# 7_Current_Sensing.net
KiCad netlist of a schematic drawn in Altium Designer
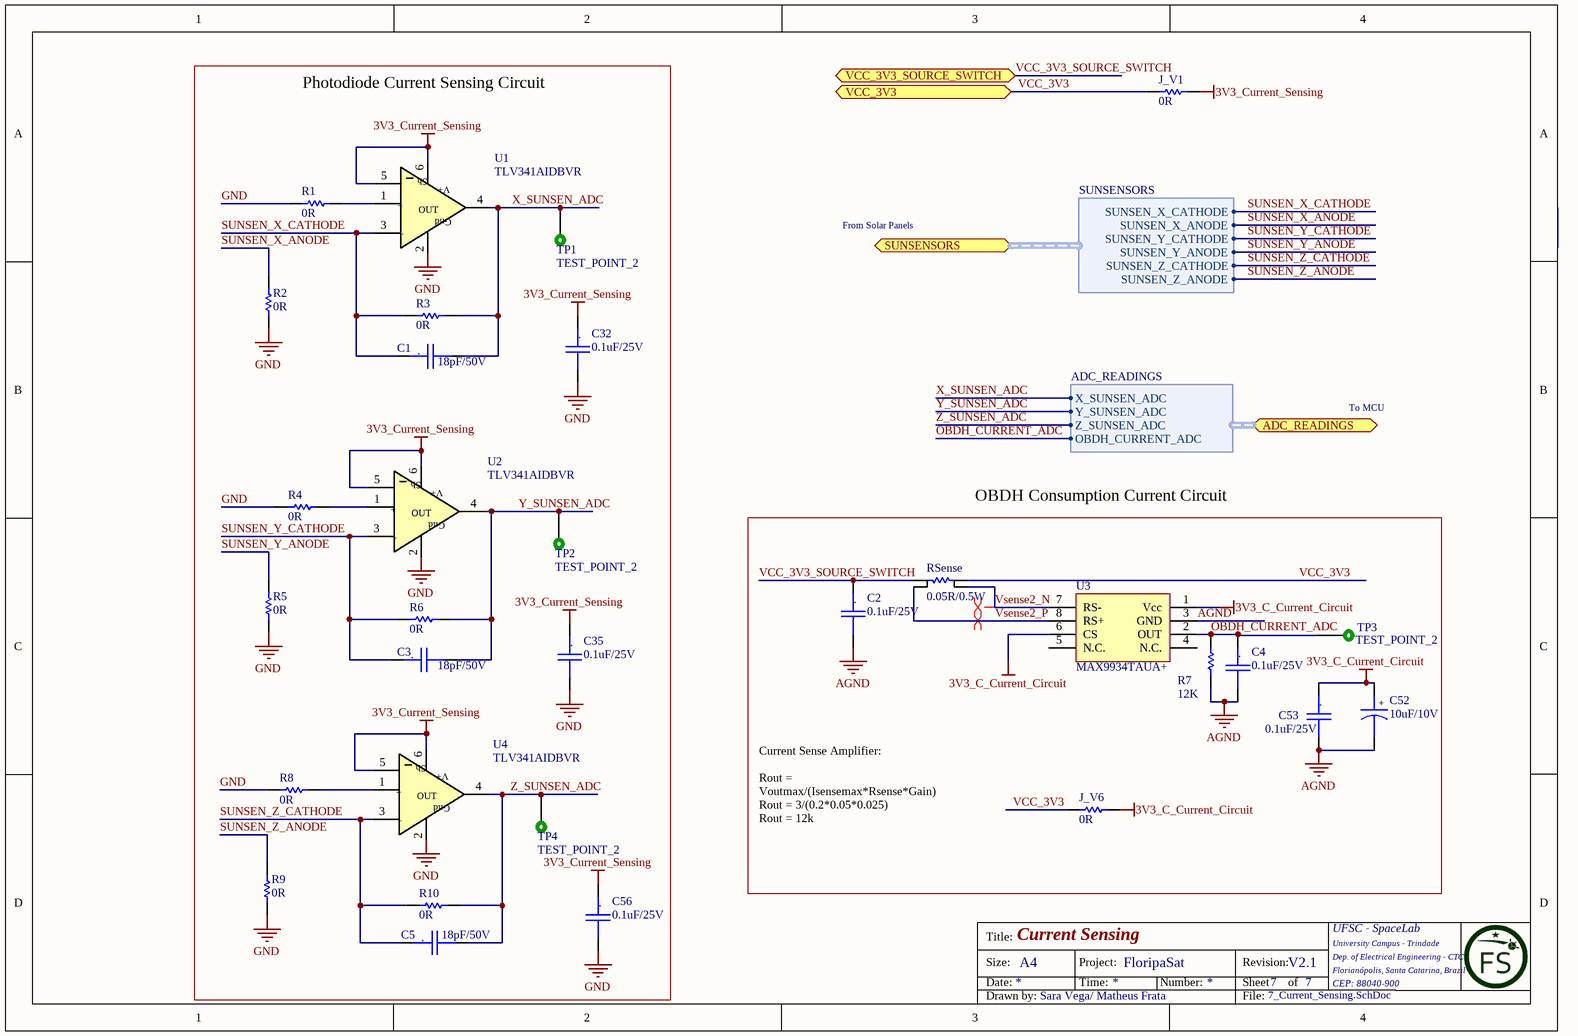
[diagram p0: 7_Current_Sensing.SchDoc]

(export (version "E")
  (design (tool "Eeschema 10.0.6"))
  (components
    (comp (ref "C1")
      (value "18pF/50V")
      (footprint "CC0805")
      (description "CAP CER 18pF 50V 5% X7R 0805")
      (fields (field (name "PARTNUMBER") "CC0805JRNPO9BN180"))
      (libsource (lib "FloripaSatSchlib") (part "Cap_Cer_X7R_18pF_50V_0805"))
    )
    (comp (ref "C2")
      (value "0.1uF/25V")
      (footprint "CC0805")
      (description "CAP CER 0.1UF 25V 10% X7R 0805")
      (fields (field (name "PARTNUMBER") "CC0805KRX7R8BB104"))
      (libsource (lib "FloripaSatSchlib") (part "Cap_Cer_X7R_0.1uF_25V_0805"))
    )
    (comp (ref "C3")
      (value "18pF/50V")
      (footprint "CC0805")
      (description "CAP CER 18pF 50V 5% X7R 0805")
      (fields (field (name "PARTNUMBER") "CC0805JRNPO9BN180"))
      (libsource (lib "FloripaSatSchlib") (part "Cap_Cer_X7R_18pF_50V_0805"))
    )
    (comp (ref "C4")
      (value "0.1uF/25V")
      (footprint "CC0805")
      (description "CAP CER 0.1UF 25V 10% X7R 0805")
      (fields (field (name "PARTNUMBER") "CC0805KRX7R8BB104"))
      (libsource (lib "FloripaSatSchlib") (part "Cap_Cer_X7R_0.1uF_25V_0805"))
    )
    (comp (ref "C5")
      (value "18pF/50V")
      (footprint "CC0805")
      (description "CAP CER 18pF 50V 5% X7R 0805")
      (fields (field (name "PARTNUMBER") "CC0805JRNPO9BN180"))
      (libsource (lib "FloripaSatSchlib") (part "Cap_Cer_X7R_18pF_50V_0805"))
    )
    (comp (ref "C32")
      (value "0.1uF/25V")
      (footprint "CC0805")
      (description "CAP CER 0.1UF 25V 10% X7R 0805")
      (fields (field (name "PARTNUMBER") "CC0805KRX7R8BB104"))
      (libsource (lib "FloripaSatSchlib") (part "Cap_Cer_X7R_0.1uF_25V_0805"))
    )
    (comp (ref "C35")
      (value "0.1uF/25V")
      (footprint "CC0805")
      (description "CAP CER 0.1UF 25V 10% X7R 0805")
      (fields (field (name "PARTNUMBER") "CC0805KRX7R8BB104"))
      (libsource (lib "FloripaSatSchlib") (part "Cap_Cer_X7R_0.1uF_25V_0805"))
    )
    (comp (ref "C52")
      (value "10uF/10V")
      (footprint "FloripaSatPcbLib:CC0805_Tantalum")
      (description "CAP Tantalum 10uF 10V 20% 0805")
      (fields (field (name "PARTNUMBER") "TPSP106M010R2000"))
      (libsource (lib "FloripaSatSchlib") (part "Cap_Tant_SMD_10uF_10V_0805"))
    )
    (comp (ref "C53")
      (value "0.1uF/25V")
      (footprint "CC0805")
      (description "CAP CER 0.1UF 25V 10% X7R 0805")
      (fields (field (name "PARTNUMBER") "CC0805KRX7R8BB104"))
      (libsource (lib "FloripaSatSchlib") (part "Cap_Cer_X7R_0.1uF_25V_0805"))
    )
    (comp (ref "C56")
      (value "0.1uF/25V")
      (footprint "CC0805")
      (description "CAP CER 0.1UF 25V 10% X7R 0805")
      (fields (field (name "PARTNUMBER") "CC0805KRX7R8BB104"))
      (libsource (lib "FloripaSatSchlib") (part "Cap_Cer_X7R_0.1uF_25V_0805"))
    )
    (comp (ref "J_V1")
      (value "0R")
      (footprint "FloripaSatPcbLib:0805")
      (description "RES 0R OHM 1/16W JUMPER 0805")
      (fields (field (name "PARTNUMBER") "CRCW08050000Z0EA"))
      (libsource (lib "FloripaSatSchlib") (part "R0R_JUMPER_1/16W_0805"))
    )
    (comp (ref "J_V6")
      (value "0R")
      (footprint "FloripaSatPcbLib:0805")
      (description "RES 0R OHM 1/16W JUMPER 0805")
      (fields (field (name "PARTNUMBER") "CRCW08050000Z0EA"))
      (libsource (lib "FloripaSatSchlib") (part "R0R_JUMPER_1/16W_0805"))
    )
    (comp (ref "R1")
      (value "0R")
      (footprint "FloripaSatPcbLib:0805")
      (description "RES 0R OHM 1/16W JUMPER 0805")
      (fields (field (name "PARTNUMBER") "CRCW08050000Z0EA"))
      (libsource (lib "FloripaSatSchlib") (part "R0R_JUMPER_1/16W_0805"))
    )
    (comp (ref "R2")
      (value "0R")
      (footprint "FloripaSatPcbLib:0805")
      (description "RES 0R OHM 1/16W JUMPER 0805")
      (fields (field (name "PARTNUMBER") "CRCW08050000Z0EA"))
      (libsource (lib "FloripaSatSchlib") (part "R0R_JUMPER_1/16W_0805"))
    )
    (comp (ref "R3")
      (value "0R")
      (footprint "FloripaSatPcbLib:0805")
      (description "RES 0R OHM 1/16W JUMPER 0805")
      (fields (field (name "PARTNUMBER") "CRCW08050000Z0EA"))
      (libsource (lib "FloripaSatSchlib") (part "R0R_JUMPER_1/16W_0805"))
    )
    (comp (ref "R4")
      (value "0R")
      (footprint "FloripaSatPcbLib:0805")
      (description "RES 0R OHM 1/16W JUMPER 0805")
      (fields (field (name "PARTNUMBER") "CRCW08050000Z0EA"))
      (libsource (lib "FloripaSatSchlib") (part "R0R_JUMPER_1/16W_0805"))
    )
    (comp (ref "R5")
      (value "0R")
      (footprint "FloripaSatPcbLib:0805")
      (description "RES 0R OHM 1/16W JUMPER 0805")
      (fields (field (name "PARTNUMBER") "CRCW08050000Z0EA"))
      (libsource (lib "FloripaSatSchlib") (part "R0R_JUMPER_1/16W_0805"))
    )
    (comp (ref "R6")
      (value "0R")
      (footprint "FloripaSatPcbLib:0805")
      (description "RES 0R OHM 1/16W JUMPER 0805")
      (fields (field (name "PARTNUMBER") "CRCW08050000Z0EA"))
      (libsource (lib "FloripaSatSchlib") (part "R0R_JUMPER_1/16W_0805"))
    )
    (comp (ref "R7")
      (value "12K")
      (footprint "0805")
      (description "RES 1.65K OHM 1/10W 0.1% 0805")
      (fields (field (name "PARTNUMBER") "PCF0805R-1K65BT1"))
      (libsource (lib "FloripaSatSchlib") (part "R1.65K_1%_1/10W_0805"))
    )
    (comp (ref "R8")
      (value "0R")
      (footprint "FloripaSatPcbLib:0805")
      (description "RES 0R OHM 1/16W JUMPER 0805")
      (fields (field (name "PARTNUMBER") "CRCW08050000Z0EA"))
      (libsource (lib "FloripaSatSchlib") (part "R0R_JUMPER_1/16W_0805"))
    )
    (comp (ref "R9")
      (value "0R")
      (footprint "FloripaSatPcbLib:0805")
      (description "RES 0R OHM 1/16W JUMPER 0805")
      (fields (field (name "PARTNUMBER") "CRCW08050000Z0EA"))
      (libsource (lib "FloripaSatSchlib") (part "R0R_JUMPER_1/16W_0805"))
    )
    (comp (ref "R10")
      (value "0R")
      (footprint "FloripaSatPcbLib:0805")
      (description "RES 0R OHM 1/16W JUMPER 0805")
      (fields (field (name "PARTNUMBER") "CRCW08050000Z0EA"))
      (libsource (lib "FloripaSatSchlib") (part "R0R_JUMPER_1/16W_0805"))
    )
    (comp (ref "RSense")
      (value "0.05R/0.5W")
      (footprint "1206 - ohmite")
      (description "Current Sense Resistors - SMD 0.05ohm .5% 4 Terminal")
      (fields (field (name "PARTNUMBER") "LVK12R050DER"))
      (libsource (lib "FloripaSatSchlib") (part "R0.05R_0.5%_0.5W_1206"))
    )
    (comp (ref "TP1")
      (value "TEST_POINT_2")
      (footprint "TEST_POINT_2")
      (description "Test point")
      (libsource (lib "FloripaSatSchlib") (part "TEST_POINT_2"))
    )
    (comp (ref "TP2")
      (value "TEST_POINT_2")
      (footprint "TEST_POINT_2")
      (description "Test point")
      (libsource (lib "FloripaSatSchlib") (part "TEST_POINT_2"))
    )
    (comp (ref "TP3")
      (value "TEST_POINT_2")
      (footprint "TEST_POINT_2")
      (description "Test point")
      (libsource (lib "FloripaSatSchlib") (part "TEST_POINT_2"))
    )
    (comp (ref "TP4")
      (value "TEST_POINT_2")
      (footprint "TEST_POINT_2")
      (description "Test point")
      (libsource (lib "FloripaSatSchlib") (part "TEST_POINT_2"))
    )
    (comp (ref "U1")
      (value "TLV341AIDBVR")
      (footprint "SOT-23 6L")
      (libsource (lib "FloripaSatSchlib") (part "TLV341AIDBVR"))
    )
    (comp (ref "U2")
      (value "TLV341AIDBVR")
      (footprint "SOT-23 6L")
      (libsource (lib "FloripaSatSchlib") (part "TLV341AIDBVR"))
    )
    (comp (ref "U3")
      (value "MAX9934TAUA+")
      (footprint "MSOP-8")
      (libsource (lib "componentes_6_11") (part "MAX9934TAUA+"))
    )
    (comp (ref "U4")
      (value "TLV341AIDBVR")
      (footprint "SOT-23 6L")
      (libsource (lib "") (part "TLV341AIDBVR_1"))
    )
  )
  (nets
    (net (code "3") (name "/OBDH_CURRENT_ADC") (class "Default")
      (node (ref "C4") (pin "1") (pinfunction "1_1") (pintype "passive"))
      (node (ref "R7") (pin "2") (pinfunction "2_2") (pintype "passive"))
      (node (ref "TP3") (pin "1") (pinfunction "1_1") (pintype "passive"))
      (node (ref "U3") (pin "2") (pinfunction "OUT_2") (pintype "passive"))
    )
    (net (code "4") (name "/SUNSEN_X_ANODE") (class "Default")
      (node (ref "R2") (pin "2") (pinfunction "2_2") (pintype "passive"))
    )
    (net (code "5") (name "/SUNSEN_X_CATHODE") (class "Default")
      (node (ref "C1") (pin "1") (pinfunction "1_1") (pintype "passive"))
      (node (ref "R3") (pin "2") (pinfunction "2_2") (pintype "passive"))
      (node (ref "U1") (pin "3") (pinfunction "-IN_3") (pintype "passive"))
    )
    (net (code "6") (name "/SUNSEN_Y_ANODE") (class "Default")
      (node (ref "R5") (pin "2") (pinfunction "2_2") (pintype "passive"))
    )
    (net (code "7") (name "/SUNSEN_Y_CATHODE") (class "Default")
      (node (ref "C3") (pin "1") (pinfunction "1_1") (pintype "passive"))
      (node (ref "R6") (pin "2") (pinfunction "2_2") (pintype "passive"))
      (node (ref "U2") (pin "3") (pinfunction "-IN_3") (pintype "passive"))
    )
    (net (code "8") (name "/SUNSEN_Z_ANODE") (class "Default")
      (node (ref "R9") (pin "2") (pinfunction "2_2") (pintype "passive"))
    )
    (net (code "9") (name "/SUNSEN_Z_CATHODE") (class "Default")
      (node (ref "C5") (pin "1") (pinfunction "1_1") (pintype "passive"))
      (node (ref "R10") (pin "2") (pinfunction "2_2") (pintype "passive"))
      (node (ref "U4") (pin "3") (pinfunction "-IN_3") (pintype "passive"))
    )
    (net (code "10") (name "/VCC_3V3") (class "Default")
      (node (ref "J_V1") (pin "2") (pinfunction "2_2") (pintype "passive"))
      (node (ref "J_V6") (pin "2") (pinfunction "2_2") (pintype "passive"))
      (node (ref "RSense") (pin "2") (pinfunction "2_2") (pintype "passive"))
    )
    (net (code "11") (name "/VCC_3V3_SOURCE_SWITCH") (class "Default")
      (node (ref "C2") (pin "1") (pinfunction "1_1") (pintype "passive"))
      (node (ref "RSense") (pin "1") (pinfunction "1_1") (pintype "passive"))
    )
    (net (code "12") (name "/Vsense2_N") (class "Default")
      (node (ref "RSense") (pin "4") (pinfunction "4_4") (pintype "passive"))
      (node (ref "U3") (pin "7") (pinfunction "RS-_7") (pintype "passive"))
    )
    (net (code "13") (name "/Vsense2_P") (class "Default")
      (node (ref "RSense") (pin "3") (pinfunction "3_3") (pintype "passive"))
      (node (ref "U3") (pin "8") (pinfunction "RS+_8") (pintype "passive"))
    )
    (net (code "14") (name "/X_SUNSEN_ADC") (class "Default")
      (node (ref "C1") (pin "2") (pinfunction "2_2") (pintype "passive"))
      (node (ref "R3") (pin "1") (pinfunction "1_1") (pintype "passive"))
      (node (ref "TP1") (pin "1") (pinfunction "1_1") (pintype "passive"))
      (node (ref "U1") (pin "4") (pinfunction "OUT_4") (pintype "passive"))
    )
    (net (code "15") (name "/Y_SUNSEN_ADC") (class "Default")
      (node (ref "C3") (pin "2") (pinfunction "2_2") (pintype "passive"))
      (node (ref "R6") (pin "1") (pinfunction "1_1") (pintype "passive"))
      (node (ref "TP2") (pin "1") (pinfunction "1_1") (pintype "passive"))
      (node (ref "U2") (pin "4") (pinfunction "OUT_4") (pintype "passive"))
    )
    (net (code "16") (name "/Z_SUNSEN_ADC") (class "Default")
      (node (ref "C5") (pin "2") (pinfunction "2_2") (pintype "passive"))
      (node (ref "R10") (pin "1") (pinfunction "1_1") (pintype "passive"))
      (node (ref "TP4") (pin "1") (pinfunction "1_1") (pintype "passive"))
      (node (ref "U4") (pin "4") (pinfunction "OUT_4") (pintype "passive"))
    )
    (net (code "19") (name "3V3_C_Current_Circuit") (class "Default")
      (node (ref "C52") (pin "1") (pinfunction "1_1") (pintype "passive"))
      (node (ref "C53") (pin "1") (pinfunction "1_1") (pintype "passive"))
      (node (ref "J_V6") (pin "1") (pinfunction "1_1") (pintype "passive"))
      (node (ref "U3") (pin "1") (pinfunction "Vcc_1") (pintype "passive"))
      (node (ref "U3") (pin "6") (pinfunction "CS_6") (pintype "passive"))
    )
    (net (code "20") (name "3V3_Current_Sensing") (class "Default")
      (node (ref "C32") (pin "1") (pinfunction "1_1") (pintype "passive"))
      (node (ref "C35") (pin "1") (pinfunction "1_1") (pintype "passive"))
      (node (ref "C56") (pin "1") (pinfunction "1_1") (pintype "passive"))
      (node (ref "J_V1") (pin "1") (pinfunction "1_1") (pintype "passive"))
      (node (ref "U1") (pin "5") (pinfunction "EN_5") (pintype "passive"))
      (node (ref "U1") (pin "6") (pinfunction "V+_6") (pintype "passive"))
      (node (ref "U2") (pin "5") (pinfunction "EN_5") (pintype "passive"))
      (node (ref "U2") (pin "6") (pinfunction "V+_6") (pintype "passive"))
      (node (ref "U4") (pin "5") (pinfunction "EN_5") (pintype "passive"))
      (node (ref "U4") (pin "6") (pinfunction "V+_6") (pintype "passive"))
    )
    (net (code "21") (name "AGND") (class "Default")
      (node (ref "C2") (pin "2") (pinfunction "2_2") (pintype "passive"))
      (node (ref "C4") (pin "2") (pinfunction "2_2") (pintype "passive"))
      (node (ref "C52") (pin "2") (pinfunction "2_2") (pintype "passive"))
      (node (ref "C53") (pin "2") (pinfunction "2_2") (pintype "passive"))
      (node (ref "R7") (pin "1") (pinfunction "1_1") (pintype "passive"))
      (node (ref "U3") (pin "3") (pinfunction "GND_3") (pintype "passive"))
    )
    (net (code "22") (name "GND") (class "Default")
      (node (ref "C32") (pin "2") (pinfunction "2_2") (pintype "passive"))
      (node (ref "C35") (pin "2") (pinfunction "2_2") (pintype "passive"))
      (node (ref "C56") (pin "2") (pinfunction "2_2") (pintype "passive"))
      (node (ref "R1") (pin "2") (pinfunction "2_2") (pintype "passive"))
      (node (ref "R2") (pin "1") (pinfunction "1_1") (pintype "passive"))
      (node (ref "R4") (pin "2") (pinfunction "2_2") (pintype "passive"))
      (node (ref "R5") (pin "1") (pinfunction "1_1") (pintype "passive"))
      (node (ref "R8") (pin "2") (pinfunction "2_2") (pintype "passive"))
      (node (ref "R9") (pin "1") (pinfunction "1_1") (pintype "passive"))
      (node (ref "U1") (pin "2") (pinfunction "Gnd_2") (pintype "passive"))
      (node (ref "U2") (pin "2") (pinfunction "Gnd_2") (pintype "passive"))
      (node (ref "U4") (pin "2") (pinfunction "Gnd_2") (pintype "passive"))
    )
    (net (code "23") (name "Net-(U1-+IN)") (class "Default")
      (node (ref "R1") (pin "1") (pinfunction "1_1") (pintype "passive"))
      (node (ref "U1") (pin "1") (pinfunction "+IN_1") (pintype "passive"))
    )
    (net (code "24") (name "Net-(U2-+IN)") (class "Default")
      (node (ref "R4") (pin "1") (pinfunction "1_1") (pintype "passive"))
      (node (ref "U2") (pin "1") (pinfunction "+IN_1") (pintype "passive"))
    )
    (net (code "25") (name "Net-(U4-+IN)") (class "Default")
      (node (ref "R8") (pin "1") (pinfunction "1_1") (pintype "passive"))
      (node (ref "U4") (pin "1") (pinfunction "+IN_1") (pintype "passive"))
    )
    (net (code "26") (name "unconnected-(U3-N.C.-Pad4)") (class "Default")
      (node (ref "U3") (pin "4") (pinfunction "N.C._4") (pintype "passive"))
    )
    (net (code "27") (name "unconnected-(U3-N.C.-Pad5)") (class "Default")
      (node (ref "U3") (pin "5") (pinfunction "N.C._5") (pintype "passive"))
    )
  )
)
